# ProPrj__MSPM0_507__2026-05-01.net
KiCad netlist of a schematic drawn in EasyEDA Pro
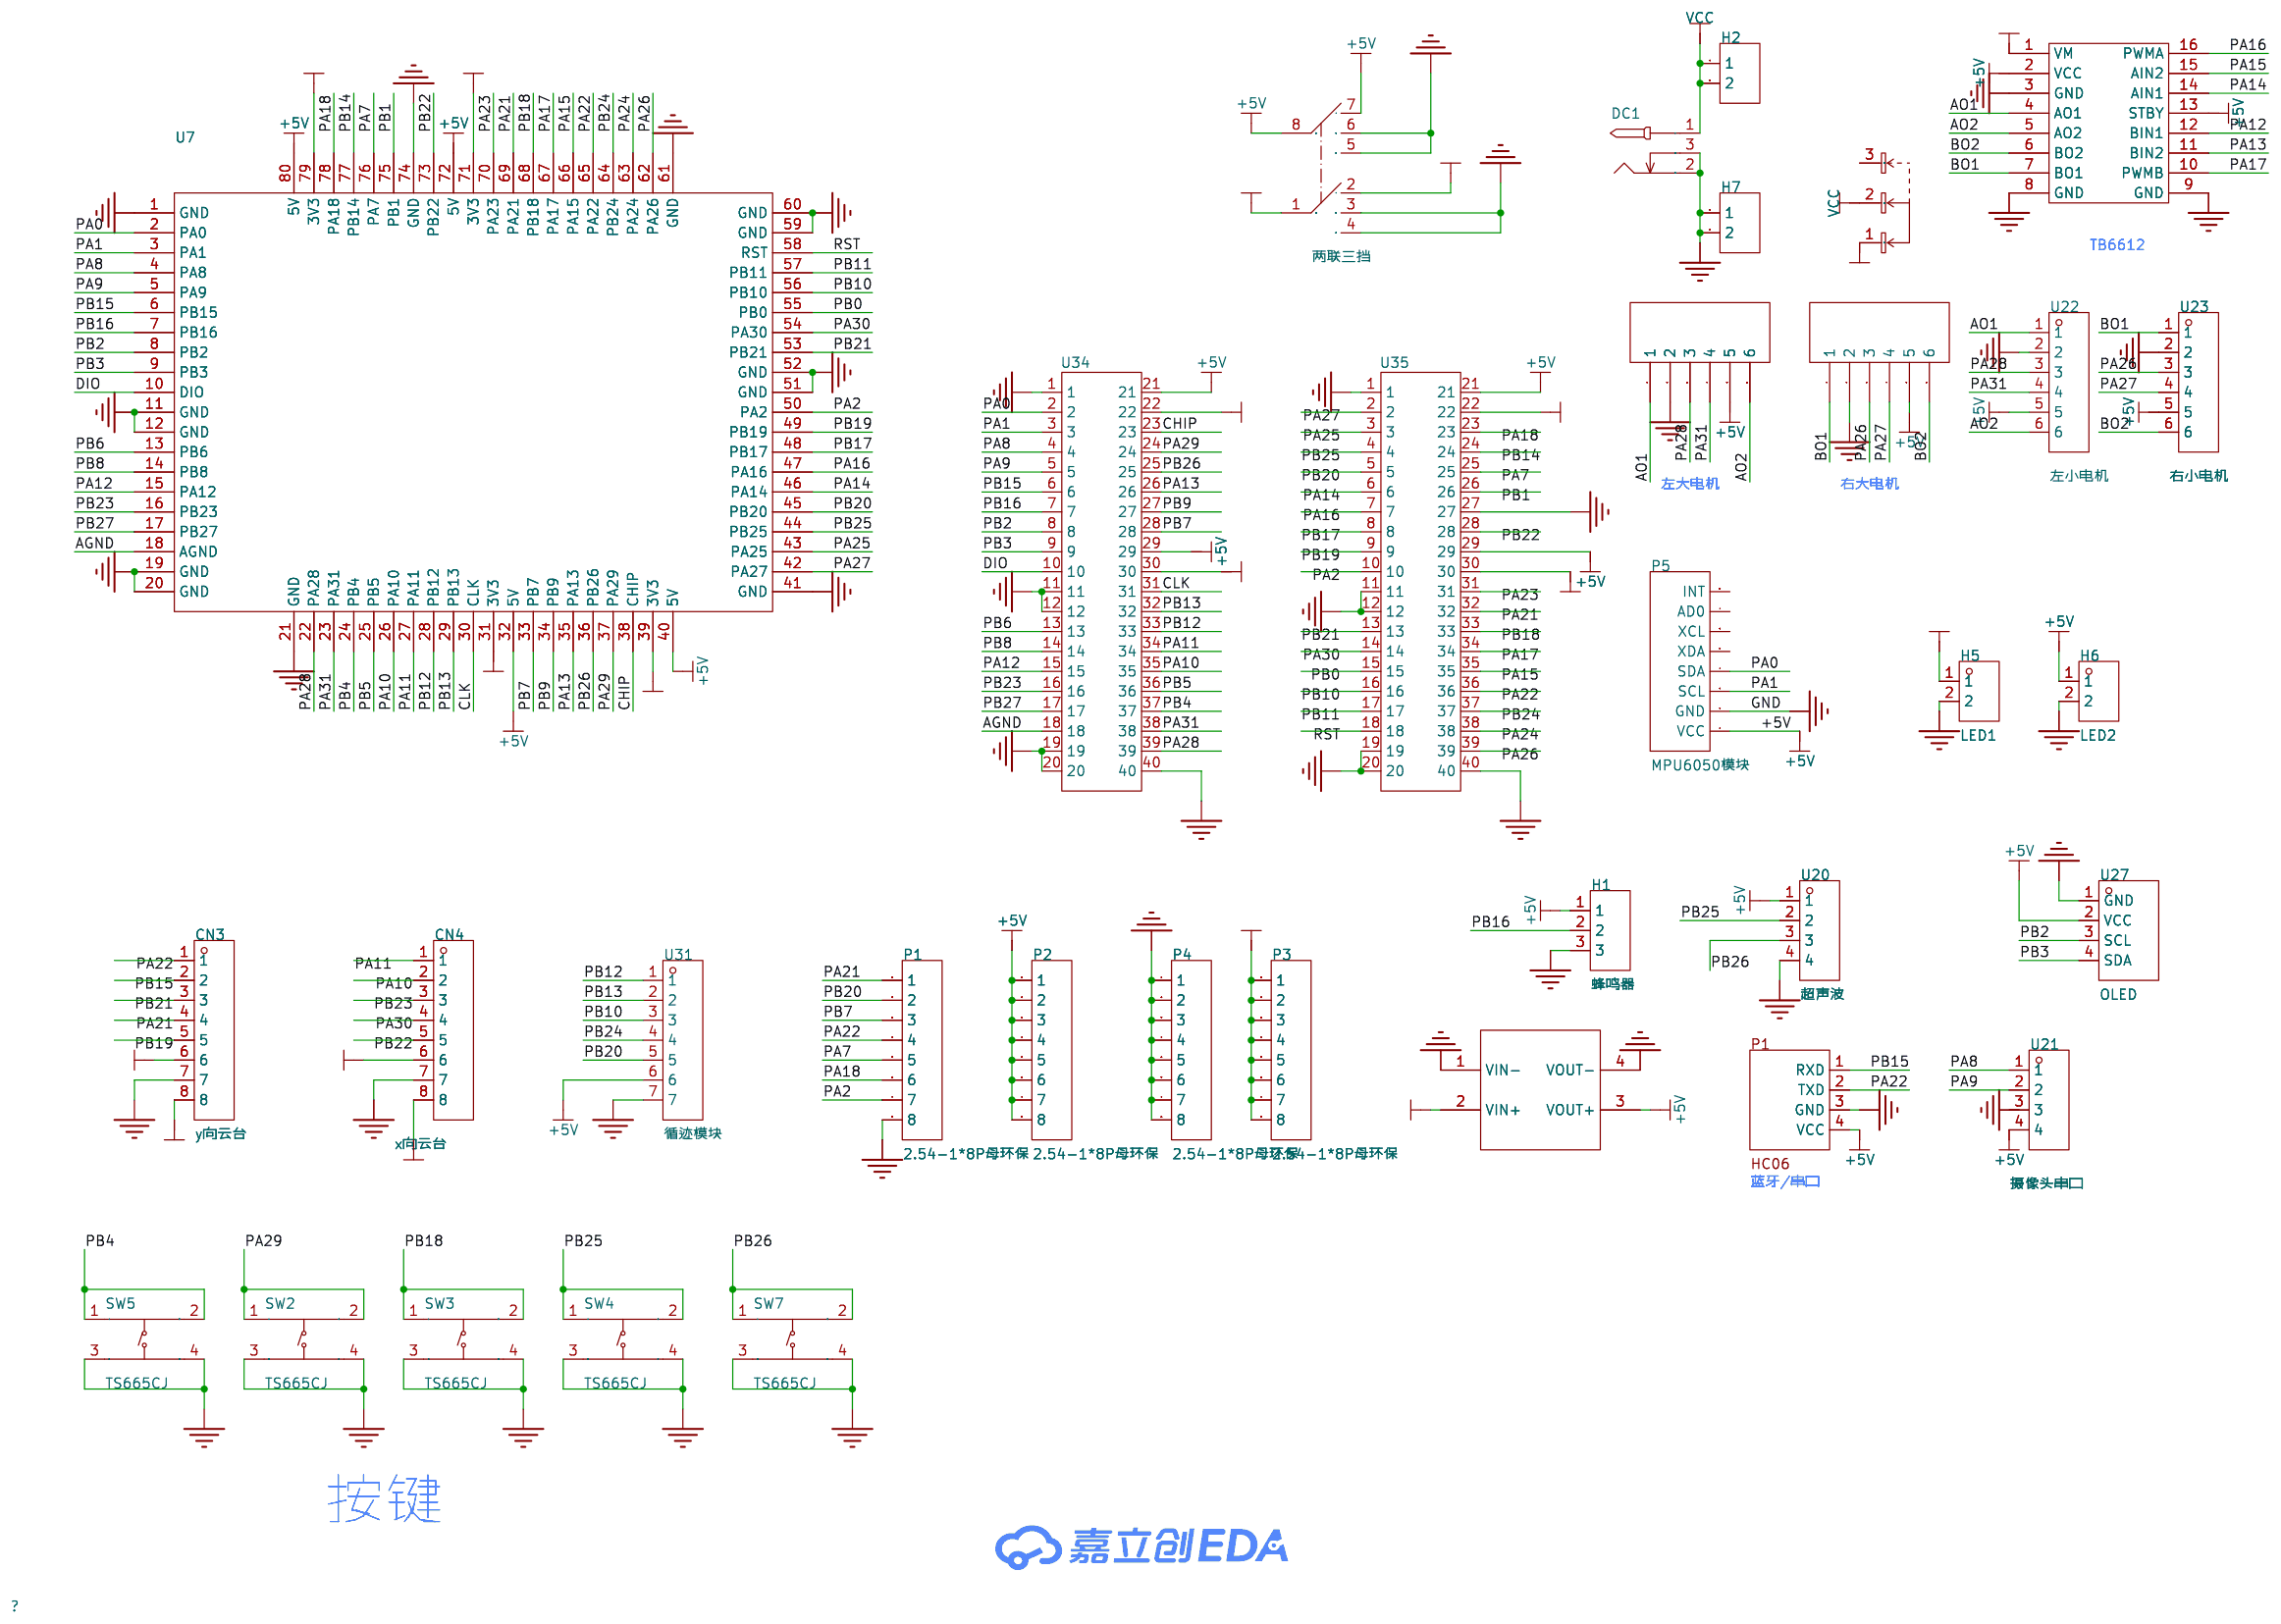
[diagram p0: schematic sheet]

(export (version "E")
  (design (tool "Eeschema 10.0.6"))
  (components
    (comp (ref "CN3")
      (value "y向云台")
      (footprint "easyedapro:CONN-TH_8P-P2.50-XH2.54-8P")
      (fields (field (name "Manufacturer") "Megastar(兆星)"))
      (libsource (lib "easyedapro") (part "ZX-XH2.54-8PZZ"))
    )
    (comp (ref "CN4")
      (value "x向云台")
      (footprint "easyedapro:CONN-TH_8P-P2.50-XH2.54-8P")
      (fields (field (name "Manufacturer") "Megastar(兆星)"))
      (libsource (lib "easyedapro") (part "ZX-XH2.54-8PZZ"))
    )
    (comp (ref "DC1")
      (value "~")
      (footprint "easyedapro:DC-005_2.5")
      (libsource (lib "easyedapro") (part "DC-005_2.5"))
    )
    (comp (ref "H1")
      (value "蜂鸣器")
      (footprint "easyedapro:HDR-TH_3P-P2.54-V-F")
      (description "插孔结构:1x3P;间距:2.54mm;行距:-;安装类型:直插;排数:单排;总孔位数:3P;塑高:-;触头材质:黄铜;触头镀层:-;")
      (fields (field (name "Manufacturer") "XFCN(兴飞)"))
      (libsource (lib "easyedapro") (part "PM254V-11-03-H85"))
    )
    (comp (ref "H2")
      (value "~")
      (footprint "easyedapro:HDR-TH_2P-P2.54-V-F")
      (libsource (lib "easyedapro") (part "Header-Female-2.54_1x2"))
    )
    (comp (ref "H5")
      (value "LED1")
      (footprint "easyedapro:HDR-TH_2P-P2.54-V-F")
      (description "插孔结构:1x2P;间距:2.54mm;行距:-;安装类型:直插;排数:单排;总孔位数:2P;塑高:-;触头材质:黄铜;触头镀层:-;")
      (fields (field (name "Manufacturer") "XFCN(兴飞)"))
      (libsource (lib "easyedapro") (part "PM254V-11-02-H85"))
    )
    (comp (ref "H6")
      (value "LED2")
      (footprint "easyedapro:HDR-TH_2P-P2.54-V-F")
      (description "插孔结构:1x2P;间距:2.54mm;行距:-;安装类型:直插;排数:单排;总孔位数:2P;塑高:-;触头材质:黄铜;触头镀层:-;")
      (fields (field (name "Manufacturer") "XFCN(兴飞)"))
      (libsource (lib "easyedapro") (part "PM254V-11-02-H85"))
    )
    (comp (ref "H7")
      (value "~")
      (footprint "easyedapro:HDR-TH_2P-P2.54-V-F")
      (libsource (lib "easyedapro") (part "Header-Female-2.54_1x2"))
    )
    (comp (ref "P1")
      (value "2.54-1*8P母环保")
      (footprint "easyedapro:HDR-TH_8P-P2.54-V-F-1")
      (description "排数:单排;总孔位数:8P;间距:2.54mm;插孔结构:1x8P;行距:-;安装类型:直插;塑高:-;触头材质:-;触头镀层:-;")
      (fields (field (name "Manufacturer") "BOOMELE(博穆精密)"))
      (libsource (lib "easyedapro") (part "Header-Female-2.54_1x8"))
    )
    (comp (ref "P2")
      (value "2.54-1*8P母环保")
      (footprint "easyedapro:HDR-TH_8P-P2.54-V-F-1")
      (description "排数:单排;总孔位数:8P;间距:2.54mm;插孔结构:1x8P;行距:-;安装类型:直插;塑高:-;触头材质:-;触头镀层:-;")
      (fields (field (name "Manufacturer") "BOOMELE(博穆精密)"))
      (libsource (lib "easyedapro") (part "Header-Female-2.54_1x8"))
    )
    (comp (ref "P3")
      (value "2.54-1*8P母环保")
      (footprint "easyedapro:HDR-TH_8P-P2.54-V-F-1")
      (description "排数:单排;总孔位数:8P;间距:2.54mm;插孔结构:1x8P;行距:-;安装类型:直插;塑高:-;触头材质:-;触头镀层:-;")
      (fields (field (name "Manufacturer") "BOOMELE(博穆精密)"))
      (libsource (lib "easyedapro") (part "Header-Female-2.54_1x8"))
    )
    (comp (ref "P4")
      (value "2.54-1*8P母环保")
      (footprint "easyedapro:HDR-TH_8P-P2.54-V-F-1")
      (description "排数:单排;总孔位数:8P;间距:2.54mm;插孔结构:1x8P;行距:-;安装类型:直插;塑高:-;触头材质:-;触头镀层:-;")
      (fields (field (name "Manufacturer") "BOOMELE(博穆精密)"))
      (libsource (lib "easyedapro") (part "Header-Female-2.54_1x8"))
    )
    (comp (ref "P5")
      (value "MPU6050模块")
      (footprint "easyedapro:MPU6050模块")
      (libsource (lib "easyedapro") (part "MPU6050模块"))
    )
    (comp (ref "SW1")
      (value "SS-12D06L5")
      (footprint "easyedapro:SW-TH_3P-P4.70_L11.1-W12.7")
      (description "电路结构:单刀双掷;安装方式:侧插;开关颜色:黑色;额定电流(DC):3A;额定电压(DC):250V;额定电流(AC):3A;额定电压(AC):250V;机械寿命:1万次;")
      (fields (field (name "Manufacturer") "XKB Connectivity(中国星坤)"))
      (libsource (lib "easyedapro") (part "SS-12D06L5"))
    )
    (comp (ref "SW2")
      (value "TS665CJ")
      (footprint "easyedapro:SW-TH_4P-L6.0-W6.0-P4.50-LS6.5")
      (description "电路结构:单刀单掷;按钮形状:圆形按钮;安装方式:直插;开关长度:6mm;开关宽度:6mm;开关高度:5mm;触点电流:50mA;额定电压(DC):12V;带灯:-;机械寿命:-;")
      (fields (field (name "Manufacturer") "SHOU HAN(首韩)"))
      (libsource (lib "easyedapro") (part "TS665CJ"))
    )
    (comp (ref "SW3")
      (value "TS665CJ")
      (footprint "easyedapro:SW-TH_4P-L6.0-W6.0-P4.50-LS6.5")
      (description "电路结构:单刀单掷;按钮形状:圆形按钮;安装方式:直插;开关长度:6mm;开关宽度:6mm;开关高度:5mm;触点电流:50mA;额定电压(DC):12V;带灯:-;机械寿命:-;")
      (fields (field (name "Manufacturer") "SHOU HAN(首韩)"))
      (libsource (lib "easyedapro") (part "TS665CJ"))
    )
    (comp (ref "SW4")
      (value "TS665CJ")
      (footprint "easyedapro:SW-TH_4P-L6.0-W6.0-P4.50-LS6.5")
      (description "电路结构:单刀单掷;按钮形状:圆形按钮;安装方式:直插;开关长度:6mm;开关宽度:6mm;开关高度:5mm;触点电流:50mA;额定电压(DC):12V;带灯:-;机械寿命:-;")
      (fields (field (name "Manufacturer") "SHOU HAN(首韩)"))
      (libsource (lib "easyedapro") (part "TS665CJ"))
    )
    (comp (ref "SW5")
      (value "TS665CJ")
      (footprint "easyedapro:SW-TH_4P-L6.0-W6.0-P4.50-LS6.5")
      (description "电路结构:单刀单掷;按钮形状:圆形按钮;安装方式:直插;开关长度:6mm;开关宽度:6mm;开关高度:5mm;触点电流:50mA;额定电压(DC):12V;带灯:-;机械寿命:-;")
      (fields (field (name "Manufacturer") "SHOU HAN(首韩)"))
      (libsource (lib "easyedapro") (part "TS665CJ"))
    )
    (comp (ref "SW7")
      (value "TS665CJ")
      (footprint "easyedapro:SW-TH_4P-L6.0-W6.0-P4.50-LS6.5")
      (description "电路结构:单刀单掷;按钮形状:圆形按钮;安装方式:直插;开关长度:6mm;开关宽度:6mm;开关高度:5mm;触点电流:50mA;额定电压(DC):12V;带灯:-;机械寿命:-;")
      (fields (field (name "Manufacturer") "SHOU HAN(首韩)"))
      (libsource (lib "easyedapro") (part "TS665CJ"))
    )
    (comp (ref "SW8")
      (value "两联三挡")
      (footprint "easyedapro:SW-TH_SS-23D07-GXXX")
      (description "SS-23D07-G060\n电路结构:双刀三掷;安装方式:直插;开关颜色:黑色;额定电流(DC):1A;\n额定电压(DC):24V;机械寿命:1万次;")
      (fields (field (name "Manufacturer") "G-Switch(品赞)"))
      (libsource (lib "easyedapro") (part "双刀三掷开关"))
    )
    (comp (ref "U2")
      (value "TB6612")
      (footprint "easyedapro:TB6612模块")
      (libsource (lib "easyedapro") (part "TB6612模块"))
    )
    (comp (ref "U4")
      (value "~")
      (footprint "easyedapro:MP1584EN模块_邮票孔")
      (description "MP1584END电源模块")
      (libsource (lib "easyedapro") (part "MP1584EN模块"))
    )
    (comp (ref "U7")
      (value "~")
      (footprint "easyedapro:嘉立创天猛星")
      (libsource (lib "easyedapro") (part "立创天猛星-MSPM0G3507"))
    )
    (comp (ref "U13")
      (value "~")
      (footprint "easyedapro:PH2.0-6")
      (libsource (lib "easyedapro") (part "PH2.0-6"))
    )
    (comp (ref "U14")
      (value "~")
      (footprint "easyedapro:PH2.0-6")
      (libsource (lib "easyedapro") (part "PH2.0-6"))
    )
    (comp (ref "U17")
      (value "~")
      (footprint "easyedapro:DIP-1X4P2.54（HC-06蓝牙模块）")
      (libsource (lib "easyedapro") (part "HC06"))
    )
    (comp (ref "U20")
      (value "超声波")
      (footprint "easyedapro:HDR-TH_4P-P2.54-V-F")
      (fields (field (name "Manufacturer") "Megastar(兆星)"))
      (libsource (lib "easyedapro") (part "ZX-PM2.54-1-4PY"))
    )
    (comp (ref "U21")
      (value "摄像头串口")
      (footprint "easyedapro:HDR-TH_4P-P2.54-V-F")
      (fields (field (name "Manufacturer") "Megastar(兆星)"))
      (libsource (lib "easyedapro") (part "ZX-PM2.54-1-4PY"))
    )
    (comp (ref "U22")
      (value "左小电机")
      (footprint "easyedapro:CONN-TH_ZH1.5-6AW_C2829757")
      (fields (field (name "Manufacturer") "Bossie(博锡)"))
      (libsource (lib "easyedapro") (part "BX-ZH1.5-6P WZ"))
    )
    (comp (ref "U23")
      (value "右小电机")
      (footprint "easyedapro:CONN-TH_ZH1.5-6AW_C2829757")
      (fields (field (name "Manufacturer") "Bossie(博锡)"))
      (libsource (lib "easyedapro") (part "BX-ZH1.5-6P WZ"))
    )
    (comp (ref "U27")
      (value "OLED")
      (footprint "easyedapro:OLED-TH_L27.8-W27.2-P2.54_C9900033791")
      (description "主控芯片:SSD1315;接口类型:I2C;尺寸(inch):0.96;像素分辨率:128x64;")
      (fields (field (name "Manufacturer") "HS(汉昇)"))
      (libsource (lib "easyedapro") (part "HS96L03W2C03"))
    )
    (comp (ref "U31")
      (value "循迹模块")
      (footprint "easyedapro:HDR-TH_7P-P2.54-V-F")
      (fields (field (name "Manufacturer") "kinghelm(金航标)"))
      (libsource (lib "easyedapro") (part "KH-2.54FH-1X7P-H8.5"))
    )
    (comp (ref "U34") (value "~") (footprint "easyedapro:20排针") (libsource (lib "easyedapro") (part "20排针")))
    (comp (ref "U35") (value "~") (footprint "easyedapro:20排针") (libsource (lib "easyedapro") (part "20排针")))
  )
  (nets
    (net (code "1") (name "+3.3V") (class "Default")
      (node (ref "CN3") (pin "6") (pinfunction "6_6") (pintype "unspecified"))
      (node (ref "CN4") (pin "6") (pinfunction "6_6") (pintype "unspecified"))
      (node (ref "H5") (pin "1") (pinfunction "1_1") (pintype "unspecified"))
      (node (ref "U34") (pin "22") (pinfunction "22_22") (pintype "unspecified"))
      (node (ref "U34") (pin "30") (pinfunction "30_30") (pintype "unspecified"))
      (node (ref "U35") (pin "22") (pinfunction "22_22") (pintype "unspecified"))
      (node (ref "U35") (pin "30") (pinfunction "30_30") (pintype "unspecified"))
      (node (ref "U7") (pin "31") (pinfunction "3V3_31") (pintype "input"))
      (node (ref "U7") (pin "39") (pinfunction "3V3_39") (pintype "input"))
      (node (ref "U7") (pin "71") (pinfunction "3V3_71") (pintype "input"))
      (node (ref "U7") (pin "79") (pinfunction "3V3_79") (pintype "input"))
    )
    (net (code "2") (name "+5V") (class "Default")
      (node (ref "H1") (pin "1") (pinfunction "1_1") (pintype "unspecified"))
      (node (ref "H6") (pin "1") (pinfunction "1_1") (pintype "unspecified"))
      (node (ref "P2") (pin "1") (pinfunction "1_1") (pintype "input"))
      (node (ref "P2") (pin "2") (pinfunction "2_2") (pintype "input"))
      (node (ref "P2") (pin "3") (pinfunction "3_3") (pintype "input"))
      (node (ref "P2") (pin "4") (pinfunction "4_4") (pintype "input"))
      (node (ref "P2") (pin "5") (pinfunction "5_5") (pintype "input"))
      (node (ref "P2") (pin "6") (pinfunction "6_6") (pintype "input"))
      (node (ref "P2") (pin "7") (pinfunction "7_7") (pintype "input"))
      (node (ref "P2") (pin "8") (pinfunction "8_8") (pintype "input"))
      (node (ref "P5") (pin "1") (pinfunction "VCC_1") (pintype "input"))
      (node (ref "SW8") (pin "7") (pinfunction "7_7") (pintype "unspecified"))
      (node (ref "SW8") (pin "8") (pinfunction "8_8") (pintype "unspecified"))
      (node (ref "U13") (pin "5") (pinfunction "5_5") (pintype "input"))
      (node (ref "U14") (pin "5") (pinfunction "5_5") (pintype "input"))
      (node (ref "U17") (pin "4") (pinfunction "VCC_4") (pintype "unspecified"))
      (node (ref "U2") (pin "13") (pinfunction "STBY_13") (pintype "input"))
      (node (ref "U2") (pin "2") (pinfunction "VCC_2") (pintype "input"))
      (node (ref "U20") (pin "1") (pinfunction "1_1") (pintype "unspecified"))
      (node (ref "U21") (pin "4") (pinfunction "4_4") (pintype "unspecified"))
      (node (ref "U22") (pin "5") (pinfunction "5_5") (pintype "unspecified"))
      (node (ref "U23") (pin "5") (pinfunction "5_5") (pintype "unspecified"))
      (node (ref "U27") (pin "2") (pinfunction "VCC_2") (pintype "unspecified"))
      (node (ref "U31") (pin "6") (pinfunction "6_6") (pintype "unspecified"))
      (node (ref "U34") (pin "21") (pinfunction "21_21") (pintype "unspecified"))
      (node (ref "U34") (pin "29") (pinfunction "29_29") (pintype "unspecified"))
      (node (ref "U35") (pin "21") (pinfunction "21_21") (pintype "unspecified"))
      (node (ref "U35") (pin "29") (pinfunction "29_29") (pintype "unspecified"))
      (node (ref "U4") (pin "3") (pinfunction "VOUT+_3") (pintype "input"))
      (node (ref "U7") (pin "32") (pinfunction "5V_32") (pintype "input"))
      (node (ref "U7") (pin "40") (pinfunction "5V_40") (pintype "input"))
      (node (ref "U7") (pin "72") (pinfunction "5V_72") (pintype "input"))
      (node (ref "U7") (pin "80") (pinfunction "5V_80") (pintype "input"))
    )
    (net (code "3") (name "+12V") (class "Default")
      (node (ref "CN3") (pin "8") (pinfunction "8_8") (pintype "unspecified"))
      (node (ref "CN4") (pin "8") (pinfunction "8_8") (pintype "unspecified"))
      (node (ref "P3") (pin "1") (pinfunction "1_1") (pintype "input"))
      (node (ref "P3") (pin "2") (pinfunction "2_2") (pintype "input"))
      (node (ref "P3") (pin "3") (pinfunction "3_3") (pintype "input"))
      (node (ref "P3") (pin "4") (pinfunction "4_4") (pintype "input"))
      (node (ref "P3") (pin "5") (pinfunction "5_5") (pintype "input"))
      (node (ref "P3") (pin "6") (pinfunction "6_6") (pintype "input"))
      (node (ref "P3") (pin "7") (pinfunction "7_7") (pintype "input"))
      (node (ref "P3") (pin "8") (pinfunction "8_8") (pintype "input"))
      (node (ref "SW1") (pin "1") (pinfunction "1_1") (pintype "unspecified"))
      (node (ref "SW8") (pin "1") (pinfunction "8_1") (pintype "unspecified"))
      (node (ref "SW8") (pin "2") (pinfunction "7_2") (pintype "unspecified"))
      (node (ref "U2") (pin "1") (pinfunction "VM_1") (pintype "input"))
      (node (ref "U4") (pin "2") (pinfunction "VIN+_2") (pintype "input"))
    )
    (net (code "4") (name "/AGND") (class "Default")
      (node (ref "U34") (pin "18") (pinfunction "18_18") (pintype "unspecified"))
      (node (ref "U7") (pin "18") (pinfunction "AGND_18") (pintype "input"))
    )
    (net (code "5") (name "/AO1") (class "Default")
      (node (ref "U13") (pin "1") (pinfunction "1_1") (pintype "input"))
      (node (ref "U2") (pin "4") (pinfunction "AO1_4") (pintype "input"))
      (node (ref "U22") (pin "1") (pinfunction "1_1") (pintype "unspecified"))
    )
    (net (code "6") (name "/AO2") (class "Default")
      (node (ref "U13") (pin "6") (pinfunction "6_6") (pintype "input"))
      (node (ref "U2") (pin "5") (pinfunction "AO2_5") (pintype "input"))
      (node (ref "U22") (pin "6") (pinfunction "6_6") (pintype "unspecified"))
    )
    (net (code "7") (name "/BO1") (class "Default")
      (node (ref "U14") (pin "1") (pinfunction "1_1") (pintype "input"))
      (node (ref "U2") (pin "7") (pinfunction "BO1_7") (pintype "input"))
      (node (ref "U23") (pin "1") (pinfunction "1_1") (pintype "unspecified"))
    )
    (net (code "8") (name "/BO2") (class "Default")
      (node (ref "U14") (pin "6") (pinfunction "6_6") (pintype "input"))
      (node (ref "U2") (pin "6") (pinfunction "BO2_6") (pintype "input"))
      (node (ref "U23") (pin "6") (pinfunction "6_6") (pintype "unspecified"))
    )
    (net (code "9") (name "/CHIP") (class "Default")
      (node (ref "U34") (pin "23") (pinfunction "23_23") (pintype "unspecified"))
      (node (ref "U7") (pin "38") (pinfunction "CHIP_38") (pintype "input"))
    )
    (net (code "10") (name "/CLK") (class "Default")
      (node (ref "U34") (pin "31") (pinfunction "31_31") (pintype "unspecified"))
      (node (ref "U7") (pin "30") (pinfunction "CLK_30") (pintype "input"))
    )
    (net (code "11") (name "/DIO") (class "Default")
      (node (ref "U34") (pin "10") (pinfunction "10_10") (pintype "unspecified"))
      (node (ref "U7") (pin "10") (pinfunction "DIO_10") (pintype "input"))
    )
    (net (code "12") (name "/PA0") (class "Default")
      (node (ref "P5") (pin "4") (pinfunction "SDA_4") (pintype "input"))
      (node (ref "U34") (pin "2") (pinfunction "2_2") (pintype "unspecified"))
      (node (ref "U7") (pin "2") (pinfunction "PA0_2") (pintype "input"))
    )
    (net (code "13") (name "/PA1") (class "Default")
      (node (ref "P5") (pin "3") (pinfunction "SCL_3") (pintype "input"))
      (node (ref "U34") (pin "3") (pinfunction "3_3") (pintype "unspecified"))
      (node (ref "U7") (pin "3") (pinfunction "PA1_3") (pintype "input"))
    )
    (net (code "14") (name "/PA2") (class "Default")
      (node (ref "P1") (pin "7") (pinfunction "7_7") (pintype "input"))
      (node (ref "U35") (pin "10") (pinfunction "10_10") (pintype "unspecified"))
      (node (ref "U7") (pin "50") (pinfunction "PA2_50") (pintype "input"))
    )
    (net (code "15") (name "/PA7") (class "Default")
      (node (ref "P1") (pin "5") (pinfunction "5_5") (pintype "input"))
      (node (ref "U35") (pin "25") (pinfunction "25_25") (pintype "unspecified"))
      (node (ref "U7") (pin "76") (pinfunction "PA7_76") (pintype "input"))
    )
    (net (code "16") (name "/PA8") (class "Default")
      (node (ref "U21") (pin "1") (pinfunction "1_1") (pintype "unspecified"))
      (node (ref "U34") (pin "4") (pinfunction "4_4") (pintype "unspecified"))
      (node (ref "U7") (pin "4") (pinfunction "PA8_4") (pintype "input"))
    )
    (net (code "17") (name "/PA9") (class "Default")
      (node (ref "U21") (pin "2") (pinfunction "2_2") (pintype "unspecified"))
      (node (ref "U34") (pin "5") (pinfunction "5_5") (pintype "unspecified"))
      (node (ref "U7") (pin "5") (pinfunction "PA9_5") (pintype "input"))
    )
    (net (code "18") (name "/PA10") (class "Default")
      (node (ref "CN4") (pin "2") (pinfunction "2_2") (pintype "unspecified"))
      (node (ref "U34") (pin "35") (pinfunction "35_35") (pintype "unspecified"))
      (node (ref "U7") (pin "26") (pinfunction "PA10_26") (pintype "input"))
    )
    (net (code "19") (name "/PA11") (class "Default")
      (node (ref "CN4") (pin "1") (pinfunction "1_1") (pintype "unspecified"))
      (node (ref "U34") (pin "34") (pinfunction "34_34") (pintype "unspecified"))
      (node (ref "U7") (pin "27") (pinfunction "PA11_27") (pintype "input"))
    )
    (net (code "20") (name "/PA12") (class "Default")
      (node (ref "U2") (pin "12") (pinfunction "BIN1_12") (pintype "input"))
      (node (ref "U34") (pin "15") (pinfunction "15_15") (pintype "unspecified"))
      (node (ref "U7") (pin "15") (pinfunction "PA12_15") (pintype "input"))
    )
    (net (code "21") (name "/PA13") (class "Default")
      (node (ref "U2") (pin "11") (pinfunction "BIN2_11") (pintype "input"))
      (node (ref "U34") (pin "26") (pinfunction "26_26") (pintype "unspecified"))
      (node (ref "U7") (pin "35") (pinfunction "PA13_35") (pintype "input"))
    )
    (net (code "22") (name "/PA14") (class "Default")
      (node (ref "U2") (pin "14") (pinfunction "AIN1_14") (pintype "input"))
      (node (ref "U35") (pin "6") (pinfunction "6_6") (pintype "unspecified"))
      (node (ref "U7") (pin "46") (pinfunction "PA14_46") (pintype "input"))
    )
    (net (code "23") (name "/PA15") (class "Default")
      (node (ref "U2") (pin "15") (pinfunction "AIN2_15") (pintype "input"))
      (node (ref "U35") (pin "35") (pinfunction "35_35") (pintype "unspecified"))
      (node (ref "U7") (pin "66") (pinfunction "PA15_66") (pintype "input"))
    )
    (net (code "24") (name "/PA16") (class "Default")
      (node (ref "U2") (pin "16") (pinfunction "PWMA_16") (pintype "input"))
      (node (ref "U35") (pin "7") (pinfunction "7_7") (pintype "unspecified"))
      (node (ref "U7") (pin "47") (pinfunction "PA16_47") (pintype "input"))
    )
    (net (code "25") (name "/PA17") (class "Default")
      (node (ref "U2") (pin "10") (pinfunction "PWMB_10") (pintype "input"))
      (node (ref "U35") (pin "34") (pinfunction "34_34") (pintype "unspecified"))
      (node (ref "U7") (pin "67") (pinfunction "PA17_67") (pintype "input"))
    )
    (net (code "26") (name "/PA18") (class "Default")
      (node (ref "P1") (pin "6") (pinfunction "6_6") (pintype "input"))
      (node (ref "U35") (pin "23") (pinfunction "23_23") (pintype "unspecified"))
      (node (ref "U7") (pin "78") (pinfunction "PA18_78") (pintype "input"))
    )
    (net (code "27") (name "/PA21") (class "Default")
      (node (ref "CN3") (pin "4") (pinfunction "4_4") (pintype "unspecified"))
      (node (ref "P1") (pin "1") (pinfunction "1_1") (pintype "input"))
      (node (ref "U35") (pin "32") (pinfunction "32_32") (pintype "unspecified"))
      (node (ref "U7") (pin "69") (pinfunction "PA21_69") (pintype "input"))
    )
    (net (code "28") (name "/PA22") (class "Default")
      (node (ref "CN3") (pin "1") (pinfunction "1_1") (pintype "unspecified"))
      (node (ref "P1") (pin "4") (pinfunction "4_4") (pintype "input"))
      (node (ref "U17") (pin "2") (pinfunction "TXD_2") (pintype "unspecified"))
      (node (ref "U35") (pin "36") (pinfunction "36_36") (pintype "unspecified"))
      (node (ref "U7") (pin "65") (pinfunction "PA22_65") (pintype "input"))
    )
    (net (code "29") (name "/PA23") (class "Default")
      (node (ref "U35") (pin "31") (pinfunction "31_31") (pintype "unspecified"))
      (node (ref "U7") (pin "70") (pinfunction "PA23_70") (pintype "input"))
    )
    (net (code "30") (name "/PA24") (class "Default")
      (node (ref "U35") (pin "38") (pinfunction "38_38") (pintype "unspecified"))
      (node (ref "U7") (pin "63") (pinfunction "PA24_63") (pintype "input"))
    )
    (net (code "31") (name "/PA25") (class "Default")
      (node (ref "U35") (pin "3") (pinfunction "3_3") (pintype "unspecified"))
      (node (ref "U7") (pin "43") (pinfunction "PA25_43") (pintype "input"))
    )
    (net (code "32") (name "/PA26") (class "Default")
      (node (ref "U14") (pin "3") (pinfunction "3_3") (pintype "input"))
      (node (ref "U23") (pin "3") (pinfunction "3_3") (pintype "unspecified"))
      (node (ref "U35") (pin "39") (pinfunction "39_39") (pintype "unspecified"))
      (node (ref "U7") (pin "62") (pinfunction "PA26_62") (pintype "input"))
    )
    (net (code "33") (name "/PA27") (class "Default")
      (node (ref "U14") (pin "4") (pinfunction "4_4") (pintype "input"))
      (node (ref "U23") (pin "4") (pinfunction "4_4") (pintype "unspecified"))
      (node (ref "U35") (pin "2") (pinfunction "2_2") (pintype "unspecified"))
      (node (ref "U7") (pin "42") (pinfunction "PA27_42") (pintype "input"))
    )
    (net (code "34") (name "/PA28") (class "Default")
      (node (ref "U13") (pin "3") (pinfunction "3_3") (pintype "input"))
      (node (ref "U22") (pin "3") (pinfunction "3_3") (pintype "unspecified"))
      (node (ref "U34") (pin "39") (pinfunction "39_39") (pintype "unspecified"))
      (node (ref "U7") (pin "22") (pinfunction "PA28_22") (pintype "input"))
    )
    (net (code "35") (name "/PA29") (class "Default")
      (node (ref "SW2") (pin "1") (pinfunction "A_1") (pintype "unspecified"))
      (node (ref "SW2") (pin "2") (pinfunction "B_2") (pintype "unspecified"))
      (node (ref "U34") (pin "24") (pinfunction "24_24") (pintype "unspecified"))
      (node (ref "U7") (pin "37") (pinfunction "PA29_37") (pintype "input"))
    )
    (net (code "36") (name "/PA30") (class "Default")
      (node (ref "CN4") (pin "4") (pinfunction "4_4") (pintype "unspecified"))
      (node (ref "U35") (pin "14") (pinfunction "14_14") (pintype "unspecified"))
      (node (ref "U7") (pin "54") (pinfunction "PA30_54") (pintype "input"))
    )
    (net (code "37") (name "/PA31") (class "Default")
      (node (ref "U13") (pin "4") (pinfunction "4_4") (pintype "input"))
      (node (ref "U22") (pin "4") (pinfunction "4_4") (pintype "unspecified"))
      (node (ref "U34") (pin "38") (pinfunction "38_38") (pintype "unspecified"))
      (node (ref "U7") (pin "23") (pinfunction "PA31_23") (pintype "input"))
    )
    (net (code "38") (name "/PB0") (class "Default")
      (node (ref "U35") (pin "15") (pinfunction "15_15") (pintype "unspecified"))
      (node (ref "U7") (pin "55") (pinfunction "PB0_55") (pintype "input"))
    )
    (net (code "39") (name "/PB1") (class "Default")
      (node (ref "U35") (pin "26") (pinfunction "26_26") (pintype "unspecified"))
      (node (ref "U7") (pin "75") (pinfunction "PB1_75") (pintype "input"))
    )
    (net (code "40") (name "/PB2") (class "Default")
      (node (ref "U27") (pin "3") (pinfunction "SCL_3") (pintype "unspecified"))
      (node (ref "U34") (pin "8") (pinfunction "8_8") (pintype "unspecified"))
      (node (ref "U7") (pin "8") (pinfunction "PB2_8") (pintype "input"))
    )
    (net (code "41") (name "/PB3") (class "Default")
      (node (ref "U27") (pin "4") (pinfunction "SDA_4") (pintype "unspecified"))
      (node (ref "U34") (pin "9") (pinfunction "9_9") (pintype "unspecified"))
      (node (ref "U7") (pin "9") (pinfunction "PB3_9") (pintype "input"))
    )
    (net (code "42") (name "/PB4") (class "Default")
      (node (ref "SW5") (pin "1") (pinfunction "A_1") (pintype "unspecified"))
      (node (ref "SW5") (pin "2") (pinfunction "B_2") (pintype "unspecified"))
      (node (ref "U34") (pin "37") (pinfunction "37_37") (pintype "unspecified"))
      (node (ref "U7") (pin "24") (pinfunction "PB4_24") (pintype "input"))
    )
    (net (code "43") (name "/PB5") (class "Default")
      (node (ref "U34") (pin "36") (pinfunction "36_36") (pintype "unspecified"))
      (node (ref "U7") (pin "25") (pinfunction "PB5_25") (pintype "input"))
    )
    (net (code "44") (name "/PB6") (class "Default")
      (node (ref "U34") (pin "13") (pinfunction "13_13") (pintype "unspecified"))
      (node (ref "U7") (pin "13") (pinfunction "PB6_13") (pintype "input"))
    )
    (net (code "45") (name "/PB7") (class "Default")
      (node (ref "P1") (pin "3") (pinfunction "3_3") (pintype "input"))
      (node (ref "U34") (pin "28") (pinfunction "28_28") (pintype "unspecified"))
      (node (ref "U7") (pin "33") (pinfunction "PB7_33") (pintype "input"))
    )
    (net (code "46") (name "/PB8") (class "Default")
      (node (ref "U34") (pin "14") (pinfunction "14_14") (pintype "unspecified"))
      (node (ref "U7") (pin "14") (pinfunction "PB8_14") (pintype "input"))
    )
    (net (code "47") (name "/PB9") (class "Default")
      (node (ref "U34") (pin "27") (pinfunction "27_27") (pintype "unspecified"))
      (node (ref "U7") (pin "34") (pinfunction "PB9_34") (pintype "input"))
    )
    (net (code "48") (name "/PB10") (class "Default")
      (node (ref "U31") (pin "3") (pinfunction "3_3") (pintype "unspecified"))
      (node (ref "U35") (pin "16") (pinfunction "16_16") (pintype "unspecified"))
      (node (ref "U7") (pin "56") (pinfunction "PB10_56") (pintype "input"))
    )
    (net (code "49") (name "/PB11") (class "Default")
      (node (ref "U35") (pin "17") (pinfunction "17_17") (pintype "unspecified"))
      (node (ref "U7") (pin "57") (pinfunction "PB11_57") (pintype "input"))
    )
    (net (code "50") (name "/PB12") (class "Default")
      (node (ref "U31") (pin "1") (pinfunction "1_1") (pintype "unspecified"))
      (node (ref "U34") (pin "33") (pinfunction "33_33") (pintype "unspecified"))
      (node (ref "U7") (pin "28") (pinfunction "PB12_28") (pintype "input"))
    )
    (net (code "51") (name "/PB13") (class "Default")
      (node (ref "U31") (pin "2") (pinfunction "2_2") (pintype "unspecified"))
      (node (ref "U34") (pin "32") (pinfunction "32_32") (pintype "unspecified"))
      (node (ref "U7") (pin "29") (pinfunction "PB13_29") (pintype "input"))
    )
    (net (code "52") (name "/PB14") (class "Default")
      (node (ref "U35") (pin "24") (pinfunction "24_24") (pintype "unspecified"))
      (node (ref "U7") (pin "77") (pinfunction "PB14_77") (pintype "input"))
    )
    (net (code "53") (name "/PB15") (class "Default")
      (node (ref "CN3") (pin "2") (pinfunction "2_2") (pintype "unspecified"))
      (node (ref "U17") (pin "1") (pinfunction "RXD_1") (pintype "unspecified"))
      (node (ref "U34") (pin "6") (pinfunction "6_6") (pintype "unspecified"))
      (node (ref "U7") (pin "6") (pinfunction "PB15_6") (pintype "input"))
    )
    (net (code "54") (name "/PB16") (class "Default")
      (node (ref "H1") (pin "2") (pinfunction "2_2") (pintype "unspecified"))
      (node (ref "U34") (pin "7") (pinfunction "7_7") (pintype "unspecified"))
      (node (ref "U7") (pin "7") (pinfunction "PB16_7") (pintype "input"))
    )
    (net (code "55") (name "/PB17") (class "Default")
      (node (ref "U35") (pin "8") (pinfunction "8_8") (pintype "unspecified"))
      (node (ref "U7") (pin "48") (pinfunction "PB17_48") (pintype "input"))
    )
    (net (code "56") (name "/PB18") (class "Default")
      (node (ref "SW3") (pin "1") (pinfunction "A_1") (pintype "unspecified"))
      (node (ref "SW3") (pin "2") (pinfunction "B_2") (pintype "unspecified"))
      (node (ref "U35") (pin "33") (pinfunction "33_33") (pintype "unspecified"))
      (node (ref "U7") (pin "68") (pinfunction "PB18_68") (pintype "input"))
    )
    (net (code "57") (name "/PB19") (class "Default")
      (node (ref "CN3") (pin "5") (pinfunction "5_5") (pintype "unspecified"))
      (node (ref "U35") (pin "9") (pinfunction "9_9") (pintype "unspecified"))
      (node (ref "U7") (pin "49") (pinfunction "PB19_49") (pintype "input"))
    )
    (net (code "58") (name "/PB20") (class "Default")
      (node (ref "P1") (pin "2") (pinfunction "2_2") (pintype "input"))
      (node (ref "U31") (pin "5") (pinfunction "5_5") (pintype "unspecified"))
      (node (ref "U35") (pin "5") (pinfunction "5_5") (pintype "unspecified"))
      (node (ref "U7") (pin "45") (pinfunction "PB20_45") (pintype "input"))
    )
    (net (code "59") (name "/PB21") (class "Default")
      (node (ref "CN3") (pin "3") (pinfunction "3_3") (pintype "unspecified"))
      (node (ref "U35") (pin "13") (pinfunction "13_13") (pintype "unspecified"))
      (node (ref "U7") (pin "53") (pinfunction "PB21_53") (pintype "input"))
    )
    (net (code "60") (name "/PB22") (class "Default")
      (node (ref "CN4") (pin "5") (pinfunction "5_5") (pintype "unspecified"))
      (node (ref "U35") (pin "28") (pinfunction "28_28") (pintype "unspecified"))
      (node (ref "U7") (pin "73") (pinfunction "PB22_73") (pintype "input"))
    )
    (net (code "61") (name "/PB23") (class "Default")
      (node (ref "CN4") (pin "3") (pinfunction "3_3") (pintype "unspecified"))
      (node (ref "U34") (pin "16") (pinfunction "16_16") (pintype "unspecified"))
      (node (ref "U7") (pin "16") (pinfunction "PB23_16") (pintype "input"))
    )
    (net (code "62") (name "/PB24") (class "Default")
      (node (ref "U31") (pin "4") (pinfunction "4_4") (pintype "unspecified"))
      (node (ref "U35") (pin "37") (pinfunction "37_37") (pintype "unspecified"))
      (node (ref "U7") (pin "64") (pinfunction "PB24_64") (pintype "input"))
    )
    (net (code "63") (name "/PB25") (class "Default")
      (node (ref "SW4") (pin "1") (pinfunction "A_1") (pintype "unspecified"))
      (node (ref "SW4") (pin "2") (pinfunction "B_2") (pintype "unspecified"))
      (node (ref "U20") (pin "2") (pinfunction "2_2") (pintype "unspecified"))
      (node (ref "U35") (pin "4") (pinfunction "4_4") (pintype "unspecified"))
      (node (ref "U7") (pin "44") (pinfunction "PB25_44") (pintype "input"))
    )
    (net (code "64") (name "/PB26") (class "Default")
      (node (ref "SW7") (pin "1") (pinfunction "A_1") (pintype "unspecified"))
      (node (ref "SW7") (pin "2") (pinfunction "B_2") (pintype "unspecified"))
      (node (ref "U20") (pin "3") (pinfunction "3_3") (pintype "unspecified"))
      (node (ref "U34") (pin "25") (pinfunction "25_25") (pintype "unspecified"))
      (node (ref "U7") (pin "36") (pinfunction "PB26_36") (pintype "input"))
    )
    (net (code "65") (name "/PB27") (class "Default")
      (node (ref "U34") (pin "17") (pinfunction "17_17") (pintype "unspecified"))
      (node (ref "U7") (pin "17") (pinfunction "PB27_17") (pintype "input"))
    )
    (net (code "66") (name "/RST") (class "Default")
      (node (ref "U35") (pin "18") (pinfunction "18_18") (pintype "unspecified"))
      (node (ref "U7") (pin "58") (pinfunction "RST_58") (pintype "input"))
    )
    (net (code "67") (name "GND") (class "Default")
      (node (ref "CN3") (pin "7") (pinfunction "7_7") (pintype "unspecified"))
      (node (ref "CN4") (pin "7") (pinfunction "7_7") (pintype "unspecified"))
      (node (ref "DC1") (pin "2") (pinfunction "2_2") (pintype "input"))
      (node (ref "DC1") (pin "3") (pinfunction "3_3") (pintype "input"))
      (node (ref "H1") (pin "3") (pinfunction "3_3") (pintype "unspecified"))
      (node (ref "H5") (pin "2") (pinfunction "2_2") (pintype "unspecified"))
      (node (ref "H6") (pin "2") (pinfunction "2_2") (pintype "unspecified"))
      (node (ref "H7") (pin "1") (pinfunction "1_1") (pintype "input"))
      (node (ref "H7") (pin "2") (pinfunction "2_2") (pintype "input"))
      (node (ref "P1") (pin "8") (pinfunction "8_8") (pintype "input"))
      (node (ref "P4") (pin "1") (pinfunction "1_1") (pintype "input"))
      (node (ref "P4") (pin "2") (pinfunction "2_2") (pintype "input"))
      (node (ref "P4") (pin "3") (pinfunction "3_3") (pintype "input"))
      (node (ref "P4") (pin "4") (pinfunction "4_4") (pintype "input"))
      (node (ref "P4") (pin "5") (pinfunction "5_5") (pintype "input"))
      (node (ref "P4") (pin "6") (pinfunction "6_6") (pintype "input"))
      (node (ref "P4") (pin "7") (pinfunction "7_7") (pintype "input"))
      (node (ref "P4") (pin "8") (pinfunction "8_8") (pintype "input"))
      (node (ref "P5") (pin "2") (pinfunction "GND_2") (pintype "input"))
      (node (ref "SW2") (pin "3") (pinfunction "C_3") (pintype "unspecified"))
      (node (ref "SW2") (pin "4") (pinfunction "D_4") (pintype "unspecified"))
      (node (ref "SW3") (pin "3") (pinfunction "C_3") (pintype "unspecified"))
      (node (ref "SW3") (pin "4") (pinfunction "D_4") (pintype "unspecified"))
      (node (ref "SW4") (pin "3") (pinfunction "C_3") (pintype "unspecified"))
      (node (ref "SW4") (pin "4") (pinfunction "D_4") (pintype "unspecified"))
      (node (ref "SW5") (pin "3") (pinfunction "C_3") (pintype "unspecified"))
      (node (ref "SW5") (pin "4") (pinfunction "D_4") (pintype "unspecified"))
      (node (ref "SW7") (pin "3") (pinfunction "C_3") (pintype "unspecified"))
      (node (ref "SW7") (pin "4") (pinfunction "D_4") (pintype "unspecified"))
      (node (ref "SW8") (pin "3") (pinfunction "6_3") (pintype "unspecified"))
      (node (ref "SW8") (pin "4") (pinfunction "5_4") (pintype "unspecified"))
      (node (ref "SW8") (pin "5") (pinfunction "5_5") (pintype "unspecified"))
      (node (ref "SW8") (pin "6") (pinfunction "6_6") (pintype "unspecified"))
      (node (ref "U13") (pin "2") (pinfunction "2_2") (pintype "input"))
      (node (ref "U14") (pin "2") (pinfunction "2_2") (pintype "input"))
      (node (ref "U17") (pin "3") (pinfunction "GND_3") (pintype "unspecified"))
      (node (ref "U2") (pin "3") (pinfunction "GND_3") (pintype "input"))
      (node (ref "U2") (pin "8") (pinfunction "GND_8") (pintype "input"))
      (node (ref "U2") (pin "9") (pinfunction "GND_9") (pintype "input"))
      (node (ref "U20") (pin "4") (pinfunction "4_4") (pintype "unspecified"))
      (node (ref "U21") (pin "3") (pinfunction "3_3") (pintype "unspecified"))
      (node (ref "U22") (pin "2") (pinfunction "2_2") (pintype "unspecified"))
      (node (ref "U23") (pin "2") (pinfunction "2_2") (pintype "unspecified"))
      (node (ref "U27") (pin "1") (pinfunction "GND_1") (pintype "unspecified"))
      (node (ref "U31") (pin "7") (pinfunction "7_7") (pintype "unspecified"))
      (node (ref "U34") (pin "1") (pinfunction "1_1") (pintype "unspecified"))
      (node (ref "U34") (pin "11") (pinfunction "11_11") (pintype "unspecified"))
      (node (ref "U34") (pin "12") (pinfunction "12_12") (pintype "unspecified"))
      (node (ref "U34") (pin "19") (pinfunction "19_19") (pintype "unspecified"))
      (node (ref "U34") (pin "20") (pinfunction "20_20") (pintype "unspecified"))
      (node (ref "U34") (pin "40") (pinfunction "40_40") (pintype "unspecified"))
      (node (ref "U35") (pin "1") (pinfunction "1_1") (pintype "unspecified"))
      (node (ref "U35") (pin "11") (pinfunction "11_11") (pintype "unspecified"))
      (node (ref "U35") (pin "12") (pinfunction "12_12") (pintype "unspecified"))
      (node (ref "U35") (pin "19") (pinfunction "19_19") (pintype "unspecified"))
      (node (ref "U35") (pin "20") (pinfunction "20_20") (pintype "unspecified"))
      (node (ref "U35") (pin "27") (pinfunction "27_27") (pintype "unspecified"))
      (node (ref "U35") (pin "40") (pinfunction "40_40") (pintype "unspecified"))
      (node (ref "U4") (pin "1") (pinfunction "VIN-_1") (pintype "input"))
      (node (ref "U4") (pin "4") (pinfunction "VOUT-_4") (pintype "input"))
      (node (ref "U7") (pin "1") (pinfunction "GND_1") (pintype "input"))
      (node (ref "U7") (pin "11") (pinfunction "GND_11") (pintype "input"))
      (node (ref "U7") (pin "12") (pinfunction "GND_12") (pintype "input"))
      (node (ref "U7") (pin "19") (pinfunction "GND_19") (pintype "input"))
      (node (ref "U7") (pin "20") (pinfunction "GND_20") (pintype "input"))
      (node (ref "U7") (pin "21") (pinfunction "GND_21") (pintype "input"))
      (node (ref "U7") (pin "41") (pinfunction "GND_41") (pintype "input"))
      (node (ref "U7") (pin "51") (pinfunction "GND_51") (pintype "input"))
      (node (ref "U7") (pin "52") (pinfunction "GND_52") (pintype "input"))
      (node (ref "U7") (pin "59") (pinfunction "GND_59") (pintype "input"))
      (node (ref "U7") (pin "60") (pinfunction "GND_60") (pintype "input"))
      (node (ref "U7") (pin "61") (pinfunction "GND_61") (pintype "input"))
      (node (ref "U7") (pin "74") (pinfunction "GND_74") (pintype "input"))
    )
    (net (code "68") (name "VCC") (class "Default")
      (node (ref "DC1") (pin "1") (pinfunction "4_1") (pintype "input"))
      (node (ref "H2") (pin "1") (pinfunction "1_1") (pintype "input"))
      (node (ref "H2") (pin "2") (pinfunction "2_2") (pintype "input"))
      (node (ref "SW1") (pin "2") (pinfunction "2_2") (pintype "unspecified"))
    )
    (net (code "69") (name "unconnected-(P5-AD0-Pad7)") (class "Default")
      (node (ref "P5") (pin "7") (pinfunction "AD0_7") (pintype "input"))
    )
    (net (code "70") (name "unconnected-(P5-INT-Pad8)") (class "Default")
      (node (ref "P5") (pin "8") (pinfunction "INT_8") (pintype "input"))
    )
    (net (code "71") (name "unconnected-(P5-XCL-Pad6)") (class "Default")
      (node (ref "P5") (pin "6") (pinfunction "XCL_6") (pintype "input"))
    )
    (net (code "72") (name "unconnected-(P5-XDA-Pad5)") (class "Default")
      (node (ref "P5") (pin "5") (pinfunction "XDA_5") (pintype "input"))
    )
    (net (code "73") (name "unconnected-(SW1-Pad3)") (class "Default")
      (node (ref "SW1") (pin "3") (pinfunction "3_3") (pintype "unspecified"))
    )
  )
)
